# bbr18_pc_battery_board.net
KiCad netlist of a schematic drawn in Altium Designer
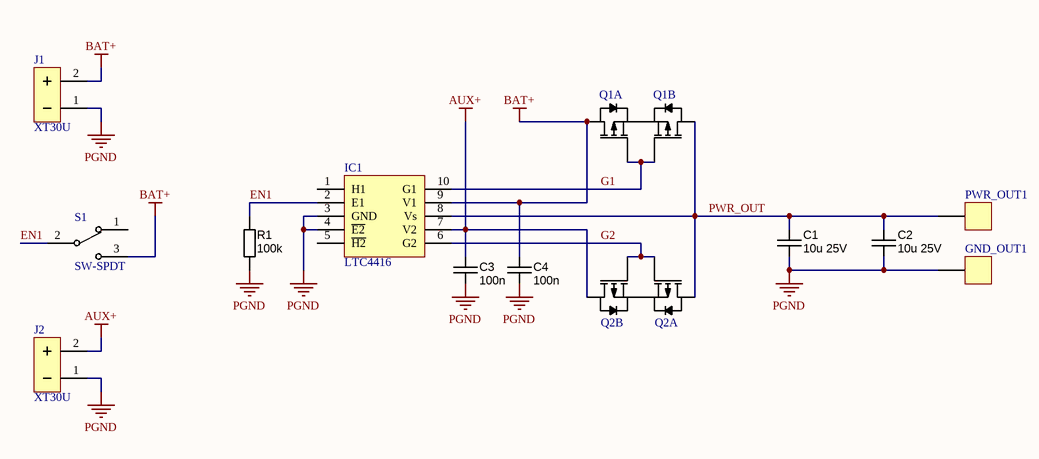
[diagram p0: bbr18_pc_battery_board.SchDoc]

(export (version "E")
  (design (tool "Eeschema 10.0.6"))
  (components
    (comp (ref "C1")
      (value "10u 25V")
      (footprint "CAPC3216X180N")
      (description "Capacitor SMD Cer 6.8nF 5% 50V NP0 1206")
      (fields (field (name "TOLERANCE") "±5%"))
      (libsource (lib "PBL - Capacitors") (part "CAPC_6n8_1206_NP0_50V"))
    )
    (comp (ref "C2")
      (value "10u 25V")
      (footprint "CAPC3216X180N")
      (description "Capacitor SMD Cer 6.8nF 5% 50V NP0 1206")
      (fields (field (name "TOLERANCE") "±5%"))
      (libsource (lib "PBL - Capacitors") (part "CAPC_6n8_1206_NP0_50V"))
    )
    (comp (ref "C3")
      (value "100n")
      (footprint "CAPC1608X90N")
      (description "Capacitor SMD Cer 10nF 10% 50V X7R 0603")
      (fields (field (name "TOLERANCE") "±10%"))
      (libsource (lib "PBL - Capacitors") (part "CAPC_10n_0603_X7R_50V_10%"))
    )
    (comp (ref "C4")
      (value "100n")
      (footprint "CAPC1608X90N")
      (description "Capacitor SMD Cer 10nF 10% 50V X7R 0603")
      (fields (field (name "TOLERANCE") "±10%"))
      (libsource (lib "PBL - Capacitors") (part "CAPC_10n_0603_X7R_50V_10%"))
    )
    (comp (ref "GND_OUT1")
      (value "HEADER-1")
      (footprint "POWER-PAD-4x3")
      (libsource (lib "connectors") (part "HEADER-1"))
    )
    (comp (ref "IC1")
      (value "LTC4416")
      (footprint "MSOP-10")
      (description "PowerPath Controller, 3.6-36V, MSOP-10, LTC4416, Linear Technology")
      (fields
        (field (name "MANUFACTURER") "Analog Devices / Linear Technology")
        (field (name "MANUFACTURER PART NUMBER") "LTC4416EMS#PBF")
      )
      (libsource (lib "digital") (part "LTC4416"))
    )
    (comp (ref "J1")
      (value "XT30U")
      (footprint "XT30U-PCB-RA-CUTOUT")
      (libsource (lib "connectors") (part "XT30U"))
    )
    (comp (ref "J2")
      (value "XT30U")
      (footprint "XT30U-PCB-RA-CUTOUT")
      (libsource (lib "connectors") (part "XT30U"))
    )
    (comp (ref "PWR_OUT1")
      (value "HEADER-1")
      (footprint "POWER-PAD-4x3")
      (libsource (lib "connectors") (part "HEADER-1"))
    )
    (comp (ref "Q1")
      (value "SI5997DU")
      (footprint "POWERPAK-CHIPFET-DUAL")
      (description "MOSFET, DUAL P-CHANNEL, 30Vin, 6A, 0.054R, SI5997DU-T1-GE3, PowerPAK ChipFET Dual")
      (fields
        (field (name "MANUFACTURER") "Vishay Siliconix")
        (field (name "MANUFACTURER PART NUMBER") "SI5997DU-T1-GE3")
      )
      (libsource (lib "mosfets") (part "SI5997DU"))
    )
    (comp (ref "Q2")
      (value "SI5997DU")
      (footprint "POWERPAK-CHIPFET-DUAL")
      (description "MOSFET, DUAL P-CHANNEL, 30Vin, 6A, 0.054R, SI5997DU-T1-GE3, PowerPAK ChipFET Dual")
      (fields
        (field (name "MANUFACTURER") "Vishay Siliconix")
        (field (name "MANUFACTURER PART NUMBER") "SI5997DU-T1-GE3")
      )
      (libsource (lib "mosfets") (part "SI5997DU"))
    )
    (comp (ref "R1")
      (value "100k")
      (footprint "RESC1608X55N")
      (description "Resistor SMD chip 100k Ohm 0.1W 1% 0603")
      (fields (field (name "TOLERANCE") "±1%") (field (name "Comment") "Thick Film"))
      (libsource (lib "PBL - Resistors") (part "RES_100K_0603_1%"))
    )
    (comp (ref "S1")
      (value "SW-SPDT")
      (footprint "A12AP-PCB-CUTOUT")
      (libsource (lib "switches") (part "SW-SPDT"))
    )
  )
  (nets
    (net (code "1") (name "/EN1") (class "Default")
      (node (ref "IC1") (pin "2") (pinfunction "E1_2") (pintype "passive"))
      (node (ref "R1") (pin "1") (pinfunction "1_1") (pintype "passive"))
      (node (ref "S1") (pin "2") (pinfunction "2_2") (pintype "passive"))
    )
    (net (code "2") (name "/G1") (class "Default")
      (node (ref "IC1") (pin "10") (pinfunction "G1_10") (pintype "passive"))
      (node (ref "Q1") (pin "G1") (pinfunction "G1_G1") (pintype "passive"))
      (node (ref "Q1") (pin "G2") (pinfunction "G2_G2") (pintype "passive"))
    )
    (net (code "3") (name "/G2") (class "Default")
      (node (ref "IC1") (pin "6") (pinfunction "G2_6") (pintype "passive"))
      (node (ref "Q2") (pin "G1") (pinfunction "G1_G1") (pintype "passive"))
      (node (ref "Q2") (pin "G2") (pinfunction "G2_G2") (pintype "passive"))
    )
    (net (code "4") (name "/PWR_OUT") (class "Default")
      (node (ref "C1") (pin "1") (pintype "passive"))
      (node (ref "C2") (pin "1") (pintype "passive"))
      (node (ref "IC1") (pin "8") (pinfunction "Vs_8") (pintype "passive"))
      (node (ref "PWR_OUT1") (pin "1") (pinfunction "1_1") (pintype "passive"))
      (node (ref "Q1") (pin "D2") (pinfunction "D2_D2") (pintype "passive"))
      (node (ref "Q2") (pin "D1") (pinfunction "D1_D1") (pintype "passive"))
    )
    (net (code "5") (name "AUX+") (class "Default")
      (node (ref "C3") (pin "1") (pintype "passive"))
      (node (ref "IC1") (pin "7") (pinfunction "V2_7") (pintype "passive"))
      (node (ref "J2") (pin "2") (pinfunction "+_2") (pintype "passive"))
      (node (ref "Q2") (pin "D2") (pinfunction "D2_D2") (pintype "passive"))
    )
    (net (code "6") (name "BAT+") (class "Default")
      (node (ref "C4") (pin "1") (pintype "passive"))
      (node (ref "IC1") (pin "9") (pinfunction "V1_9") (pintype "passive"))
      (node (ref "J1") (pin "2") (pinfunction "+_2") (pintype "passive"))
      (node (ref "Q1") (pin "D1") (pinfunction "D1_D1") (pintype "passive"))
      (node (ref "S1") (pin "3") (pinfunction "3_3") (pintype "passive"))
    )
    (net (code "7") (name "Net-(Q1-PadS1)") (class "Default")
      (node (ref "Q1") (pin "S1") (pinfunction "S1_S1") (pintype "passive"))
      (node (ref "Q1") (pin "S2") (pinfunction "S2_S2") (pintype "passive"))
    )
    (net (code "8") (name "Net-(Q2-PadS1)") (class "Default")
      (node (ref "Q2") (pin "S1") (pinfunction "S1_S1") (pintype "passive"))
      (node (ref "Q2") (pin "S2") (pinfunction "S2_S2") (pintype "passive"))
    )
    (net (code "9") (name "PGND") (class "Default")
      (node (ref "C1") (pin "2") (pintype "passive"))
      (node (ref "C2") (pin "2") (pintype "passive"))
      (node (ref "C3") (pin "2") (pintype "passive"))
      (node (ref "C4") (pin "2") (pintype "passive"))
      (node (ref "GND_OUT1") (pin "1") (pinfunction "1_1") (pintype "passive"))
      (node (ref "IC1") (pin "3") (pinfunction "GND_3") (pintype "passive"))
      (node (ref "IC1") (pin "4") (pinfunction "~{E2}_4") (pintype "passive"))
      (node (ref "J1") (pin "1") (pinfunction "-_1") (pintype "passive"))
      (node (ref "J2") (pin "1") (pinfunction "-_1") (pintype "passive"))
      (node (ref "R1") (pin "2") (pinfunction "2_2") (pintype "passive"))
    )
    (net (code "10") (name "unconnected-(IC1-H1-Pad1)") (class "Default")
      (node (ref "IC1") (pin "1") (pinfunction "H1_1") (pintype "passive"))
    )
    (net (code "11") (name "unconnected-(IC1-~{H2}-Pad5)") (class "Default")
      (node (ref "IC1") (pin "5") (pinfunction "~{H2}_5") (pintype "passive"))
    )
    (net (code "12") (name "unconnected-(S1-Pad1)") (class "Default")
      (node (ref "S1") (pin "1") (pinfunction "1_1") (pintype "passive"))
    )
  )
)
